# Kube-Module-ADIO.net
KiCad netlist of a schematic drawn in EAGLE
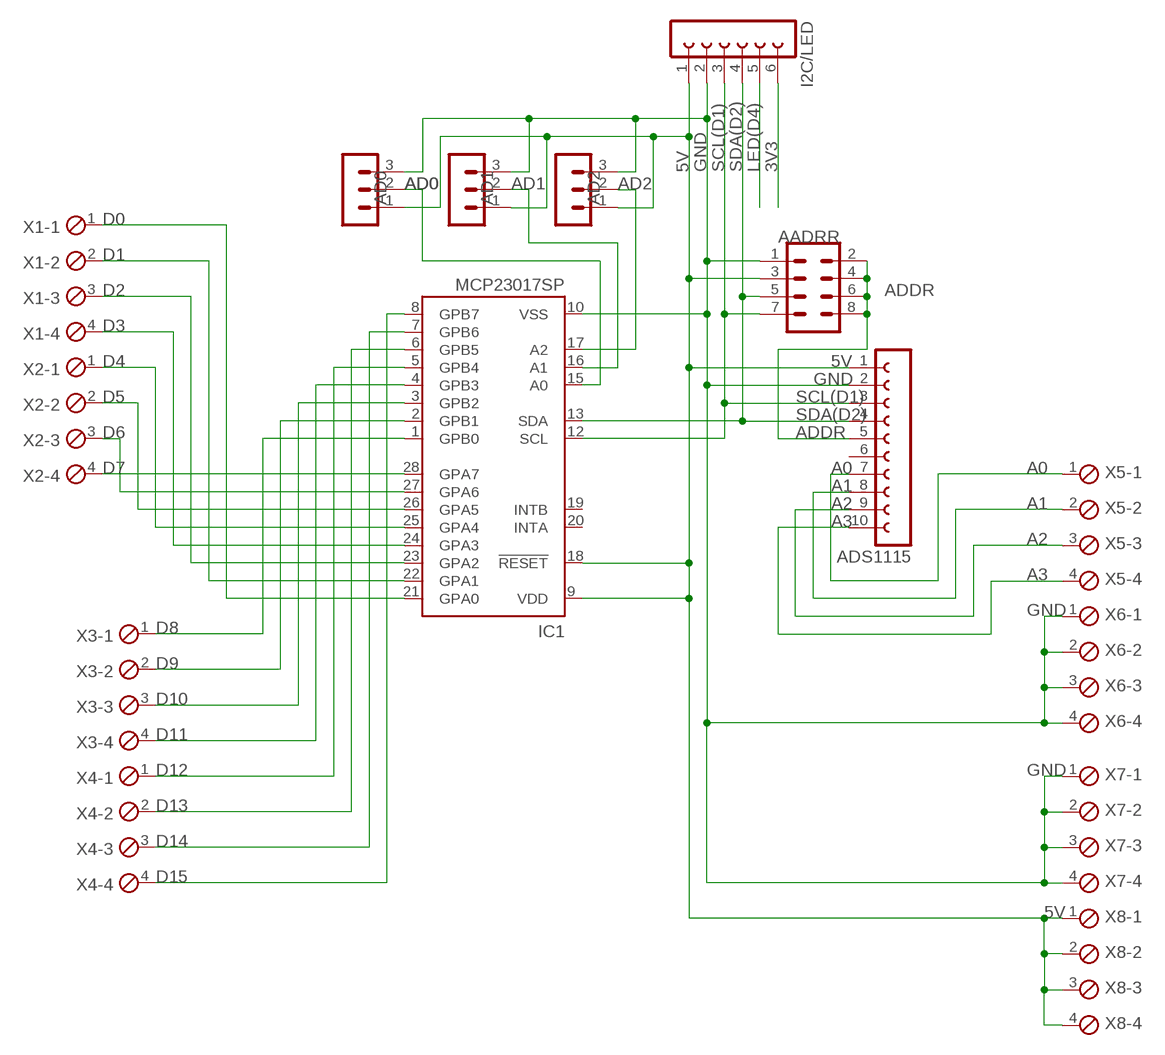
[diagram p0: schematic, sheet 1]

(export (version "E")
  (design (tool "Eeschema 10.0.6"))
  (components
    (comp (ref "AADRR")
      (value "MA04-2")
      (footprint "eagle-import:MA04-2")
      (libsource (lib "eagle-import") (part "MA04-2"))
    )
    (comp (ref "AD0")
      (value "MA03-1")
      (footprint "eagle-import:MA03-1")
      (libsource (lib "eagle-import") (part "MA03-1"))
    )
    (comp (ref "AD1")
      (value "MA03-1")
      (footprint "eagle-import:MA03-1")
      (libsource (lib "eagle-import") (part "MA03-1"))
    )
    (comp (ref "AD2")
      (value "MA03-1")
      (footprint "eagle-import:MA03-1")
      (libsource (lib "eagle-import") (part "MA03-1"))
    )
    (comp (ref "ADS1115")
      (value "FE10W")
      (footprint "eagle-import:FE10W")
      (libsource (lib "eagle-import") (part "FE10W"))
    )
    (comp (ref "I2C/LED")
      (value "FE06-1")
      (footprint "eagle-import:FE06")
      (libsource (lib "eagle-import") (part "FE06-1"))
    )
    (comp (ref "IC1")
      (value "MCP23017SP")
      (footprint "eagle-import:DIL28-3")
      (libsource (lib "eagle-import") (part "MCP23017SP"))
    )
    (comp (ref "X1")
      (value "MPT4")
      (footprint "eagle-import:4POL254")
      (libsource (lib "eagle-import") (part "MPT4"))
    )
    (comp (ref "X2")
      (value "MPT4")
      (footprint "eagle-import:4POL254")
      (libsource (lib "eagle-import") (part "MPT4"))
    )
    (comp (ref "X3")
      (value "MPT4")
      (footprint "eagle-import:4POL254")
      (libsource (lib "eagle-import") (part "MPT4"))
    )
    (comp (ref "X4")
      (value "MPT4")
      (footprint "eagle-import:4POL254")
      (libsource (lib "eagle-import") (part "MPT4"))
    )
    (comp (ref "X5")
      (value "MPT4")
      (footprint "eagle-import:4POL254")
      (libsource (lib "eagle-import") (part "MPT4"))
    )
    (comp (ref "X6")
      (value "MPT4")
      (footprint "eagle-import:4POL254")
      (libsource (lib "eagle-import") (part "MPT4"))
    )
    (comp (ref "X7")
      (value "MPT4")
      (footprint "eagle-import:4POL254")
      (libsource (lib "eagle-import") (part "MPT4"))
    )
    (comp (ref "X8")
      (value "MPT4")
      (footprint "eagle-import:4POL254")
      (libsource (lib "eagle-import") (part "MPT4"))
    )
  )
  (nets
    (net (code "1") (name "/3V3") (class "Default")
      (node (ref "I2C/LED") (pin "6") (pinfunction "6_6") (pintype "passive"))
    )
    (net (code "2") (name "/5V") (class "Default")
      (node (ref "AADRR") (pin "3") (pinfunction "3_3") (pintype "passive"))
      (node (ref "AD0") (pin "1") (pinfunction "1_1") (pintype "passive"))
      (node (ref "AD1") (pin "1") (pinfunction "1_1") (pintype "passive"))
      (node (ref "AD2") (pin "1") (pinfunction "1_1") (pintype "passive"))
      (node (ref "ADS1115") (pin "1") (pinfunction "1_1") (pintype "passive"))
      (node (ref "I2C/LED") (pin "1") (pinfunction "1_1") (pintype "passive"))
      (node (ref "IC1") (pin "18") (pinfunction "~{RESET}_18") (pintype "input"))
      (node (ref "IC1") (pin "9") (pinfunction "VDD_9") (pintype "power_in"))
      (node (ref "X8") (pin "1") (pinfunction "1_1") (pintype "passive"))
      (node (ref "X8") (pin "2") (pinfunction "1_2") (pintype "passive"))
      (node (ref "X8") (pin "3") (pinfunction "1_3") (pintype "passive"))
      (node (ref "X8") (pin "4") (pinfunction "1_4") (pintype "passive"))
    )
    (net (code "3") (name "/A0") (class "Default")
      (node (ref "ADS1115") (pin "7") (pinfunction "7_7") (pintype "passive"))
      (node (ref "X5") (pin "1") (pinfunction "1_1") (pintype "passive"))
    )
    (net (code "4") (name "/A1") (class "Default")
      (node (ref "ADS1115") (pin "8") (pinfunction "8_8") (pintype "passive"))
      (node (ref "X5") (pin "2") (pinfunction "1_2") (pintype "passive"))
    )
    (net (code "5") (name "/A2") (class "Default")
      (node (ref "ADS1115") (pin "9") (pinfunction "9_9") (pintype "passive"))
      (node (ref "X5") (pin "3") (pinfunction "1_3") (pintype "passive"))
    )
    (net (code "6") (name "/A3") (class "Default")
      (node (ref "ADS1115") (pin "10") (pinfunction "10_10") (pintype "passive"))
      (node (ref "X5") (pin "4") (pinfunction "1_4") (pintype "passive"))
    )
    (net (code "7") (name "/AD0") (class "Default")
      (node (ref "AD0") (pin "2") (pinfunction "2_2") (pintype "passive"))
      (node (ref "IC1") (pin "15") (pinfunction "A0_15") (pintype "input"))
    )
    (net (code "8") (name "/AD1") (class "Default")
      (node (ref "AD1") (pin "2") (pinfunction "2_2") (pintype "passive"))
      (node (ref "IC1") (pin "16") (pinfunction "A1_16") (pintype "input"))
    )
    (net (code "9") (name "/AD2") (class "Default")
      (node (ref "AD2") (pin "2") (pinfunction "2_2") (pintype "passive"))
      (node (ref "IC1") (pin "17") (pinfunction "A2_17") (pintype "input"))
    )
    (net (code "10") (name "/ADDR") (class "Default")
      (node (ref "AADRR") (pin "2") (pinfunction "2_2") (pintype "passive"))
      (node (ref "AADRR") (pin "4") (pinfunction "4_4") (pintype "passive"))
      (node (ref "AADRR") (pin "6") (pinfunction "6_6") (pintype "passive"))
      (node (ref "AADRR") (pin "8") (pinfunction "8_8") (pintype "passive"))
      (node (ref "ADS1115") (pin "5") (pinfunction "5_5") (pintype "passive"))
    )
    (net (code "11") (name "/D0") (class "Default")
      (node (ref "IC1") (pin "21") (pinfunction "GPA0_21") (pintype "bidirectional"))
      (node (ref "X1") (pin "1") (pinfunction "1_1") (pintype "passive"))
    )
    (net (code "12") (name "/D1") (class "Default")
      (node (ref "IC1") (pin "22") (pinfunction "GPA1_22") (pintype "bidirectional"))
      (node (ref "X1") (pin "2") (pinfunction "1_2") (pintype "passive"))
    )
    (net (code "13") (name "/D2") (class "Default")
      (node (ref "IC1") (pin "23") (pinfunction "GPA2_23") (pintype "bidirectional"))
      (node (ref "X1") (pin "3") (pinfunction "1_3") (pintype "passive"))
    )
    (net (code "14") (name "/D3") (class "Default")
      (node (ref "IC1") (pin "24") (pinfunction "GPA3_24") (pintype "bidirectional"))
      (node (ref "X1") (pin "4") (pinfunction "1_4") (pintype "passive"))
    )
    (net (code "15") (name "/D4") (class "Default")
      (node (ref "IC1") (pin "25") (pinfunction "GPA4_25") (pintype "bidirectional"))
      (node (ref "X2") (pin "1") (pinfunction "1_1") (pintype "passive"))
    )
    (net (code "16") (name "/D5") (class "Default")
      (node (ref "IC1") (pin "26") (pinfunction "GPA5_26") (pintype "bidirectional"))
      (node (ref "X2") (pin "2") (pinfunction "1_2") (pintype "passive"))
    )
    (net (code "17") (name "/D6") (class "Default")
      (node (ref "IC1") (pin "27") (pinfunction "GPA6_27") (pintype "bidirectional"))
      (node (ref "X2") (pin "3") (pinfunction "1_3") (pintype "passive"))
    )
    (net (code "18") (name "/D7") (class "Default")
      (node (ref "IC1") (pin "28") (pinfunction "GPA7_28") (pintype "bidirectional"))
      (node (ref "X2") (pin "4") (pinfunction "1_4") (pintype "passive"))
    )
    (net (code "19") (name "/D8") (class "Default")
      (node (ref "IC1") (pin "1") (pinfunction "GPB0_1") (pintype "bidirectional"))
      (node (ref "X3") (pin "1") (pinfunction "1_1") (pintype "passive"))
    )
    (net (code "20") (name "/D9") (class "Default")
      (node (ref "IC1") (pin "2") (pinfunction "GPB1_2") (pintype "bidirectional"))
      (node (ref "X3") (pin "2") (pinfunction "1_2") (pintype "passive"))
    )
    (net (code "21") (name "/D10") (class "Default")
      (node (ref "IC1") (pin "3") (pinfunction "GPB2_3") (pintype "bidirectional"))
      (node (ref "X3") (pin "3") (pinfunction "1_3") (pintype "passive"))
    )
    (net (code "22") (name "/D11") (class "Default")
      (node (ref "IC1") (pin "4") (pinfunction "GPB3_4") (pintype "bidirectional"))
      (node (ref "X3") (pin "4") (pinfunction "1_4") (pintype "passive"))
    )
    (net (code "23") (name "/D12") (class "Default")
      (node (ref "IC1") (pin "5") (pinfunction "GPB4_5") (pintype "bidirectional"))
      (node (ref "X4") (pin "1") (pinfunction "1_1") (pintype "passive"))
    )
    (net (code "24") (name "/D13") (class "Default")
      (node (ref "IC1") (pin "6") (pinfunction "GPB5_6") (pintype "bidirectional"))
      (node (ref "X4") (pin "2") (pinfunction "1_2") (pintype "passive"))
    )
    (net (code "25") (name "/D14") (class "Default")
      (node (ref "IC1") (pin "7") (pinfunction "GPB6_7") (pintype "bidirectional"))
      (node (ref "X4") (pin "3") (pinfunction "1_3") (pintype "passive"))
    )
    (net (code "26") (name "/D15") (class "Default")
      (node (ref "IC1") (pin "8") (pinfunction "GPB7_8") (pintype "bidirectional"))
      (node (ref "X4") (pin "4") (pinfunction "1_4") (pintype "passive"))
    )
    (net (code "27") (name "/GND") (class "Default")
      (node (ref "AADRR") (pin "1") (pinfunction "1_1") (pintype "passive"))
      (node (ref "AD0") (pin "3") (pinfunction "3_3") (pintype "passive"))
      (node (ref "AD1") (pin "3") (pinfunction "3_3") (pintype "passive"))
      (node (ref "AD2") (pin "3") (pinfunction "3_3") (pintype "passive"))
      (node (ref "ADS1115") (pin "2") (pinfunction "2_2") (pintype "passive"))
      (node (ref "I2C/LED") (pin "2") (pinfunction "2_2") (pintype "passive"))
      (node (ref "IC1") (pin "10") (pinfunction "VSS_10") (pintype "power_in"))
      (node (ref "X6") (pin "1") (pinfunction "1_1") (pintype "passive"))
      (node (ref "X6") (pin "2") (pinfunction "1_2") (pintype "passive"))
      (node (ref "X6") (pin "3") (pinfunction "1_3") (pintype "passive"))
      (node (ref "X6") (pin "4") (pinfunction "1_4") (pintype "passive"))
      (node (ref "X7") (pin "1") (pinfunction "1_1") (pintype "passive"))
      (node (ref "X7") (pin "2") (pinfunction "1_2") (pintype "passive"))
      (node (ref "X7") (pin "3") (pinfunction "1_3") (pintype "passive"))
      (node (ref "X7") (pin "4") (pinfunction "1_4") (pintype "passive"))
    )
    (net (code "28") (name "/LED(D4)") (class "Default")
      (node (ref "I2C/LED") (pin "5") (pinfunction "5_5") (pintype "passive"))
    )
    (net (code "29") (name "/SCL(D1)") (class "Default")
      (node (ref "AADRR") (pin "7") (pinfunction "7_7") (pintype "passive"))
      (node (ref "ADS1115") (pin "3") (pinfunction "3_3") (pintype "passive"))
      (node (ref "I2C/LED") (pin "3") (pinfunction "3_3") (pintype "passive"))
      (node (ref "IC1") (pin "12") (pinfunction "SCL_12") (pintype "input"))
    )
    (net (code "30") (name "/SDA(D2)") (class "Default")
      (node (ref "AADRR") (pin "5") (pinfunction "5_5") (pintype "passive"))
      (node (ref "ADS1115") (pin "4") (pinfunction "4_4") (pintype "passive"))
      (node (ref "I2C/LED") (pin "4") (pinfunction "4_4") (pintype "passive"))
      (node (ref "IC1") (pin "13") (pinfunction "SDA_13") (pintype "bidirectional"))
    )
    (net (code "31") (name "unconnected-(ADS1115-Pad6)") (class "Default")
      (node (ref "ADS1115") (pin "6") (pinfunction "6_6") (pintype "passive"))
    )
    (net (code "32") (name "unconnected-(IC1-INTA-Pad20)") (class "Default")
      (node (ref "IC1") (pin "20") (pinfunction "INTA_20") (pintype "output"))
    )
    (net (code "33") (name "unconnected-(IC1-INTB-Pad19)") (class "Default")
      (node (ref "IC1") (pin "19") (pinfunction "INTB_19") (pintype "output"))
    )
  )
)
